# Pyro.net
KiCad netlist of a schematic drawn in Altium Designer
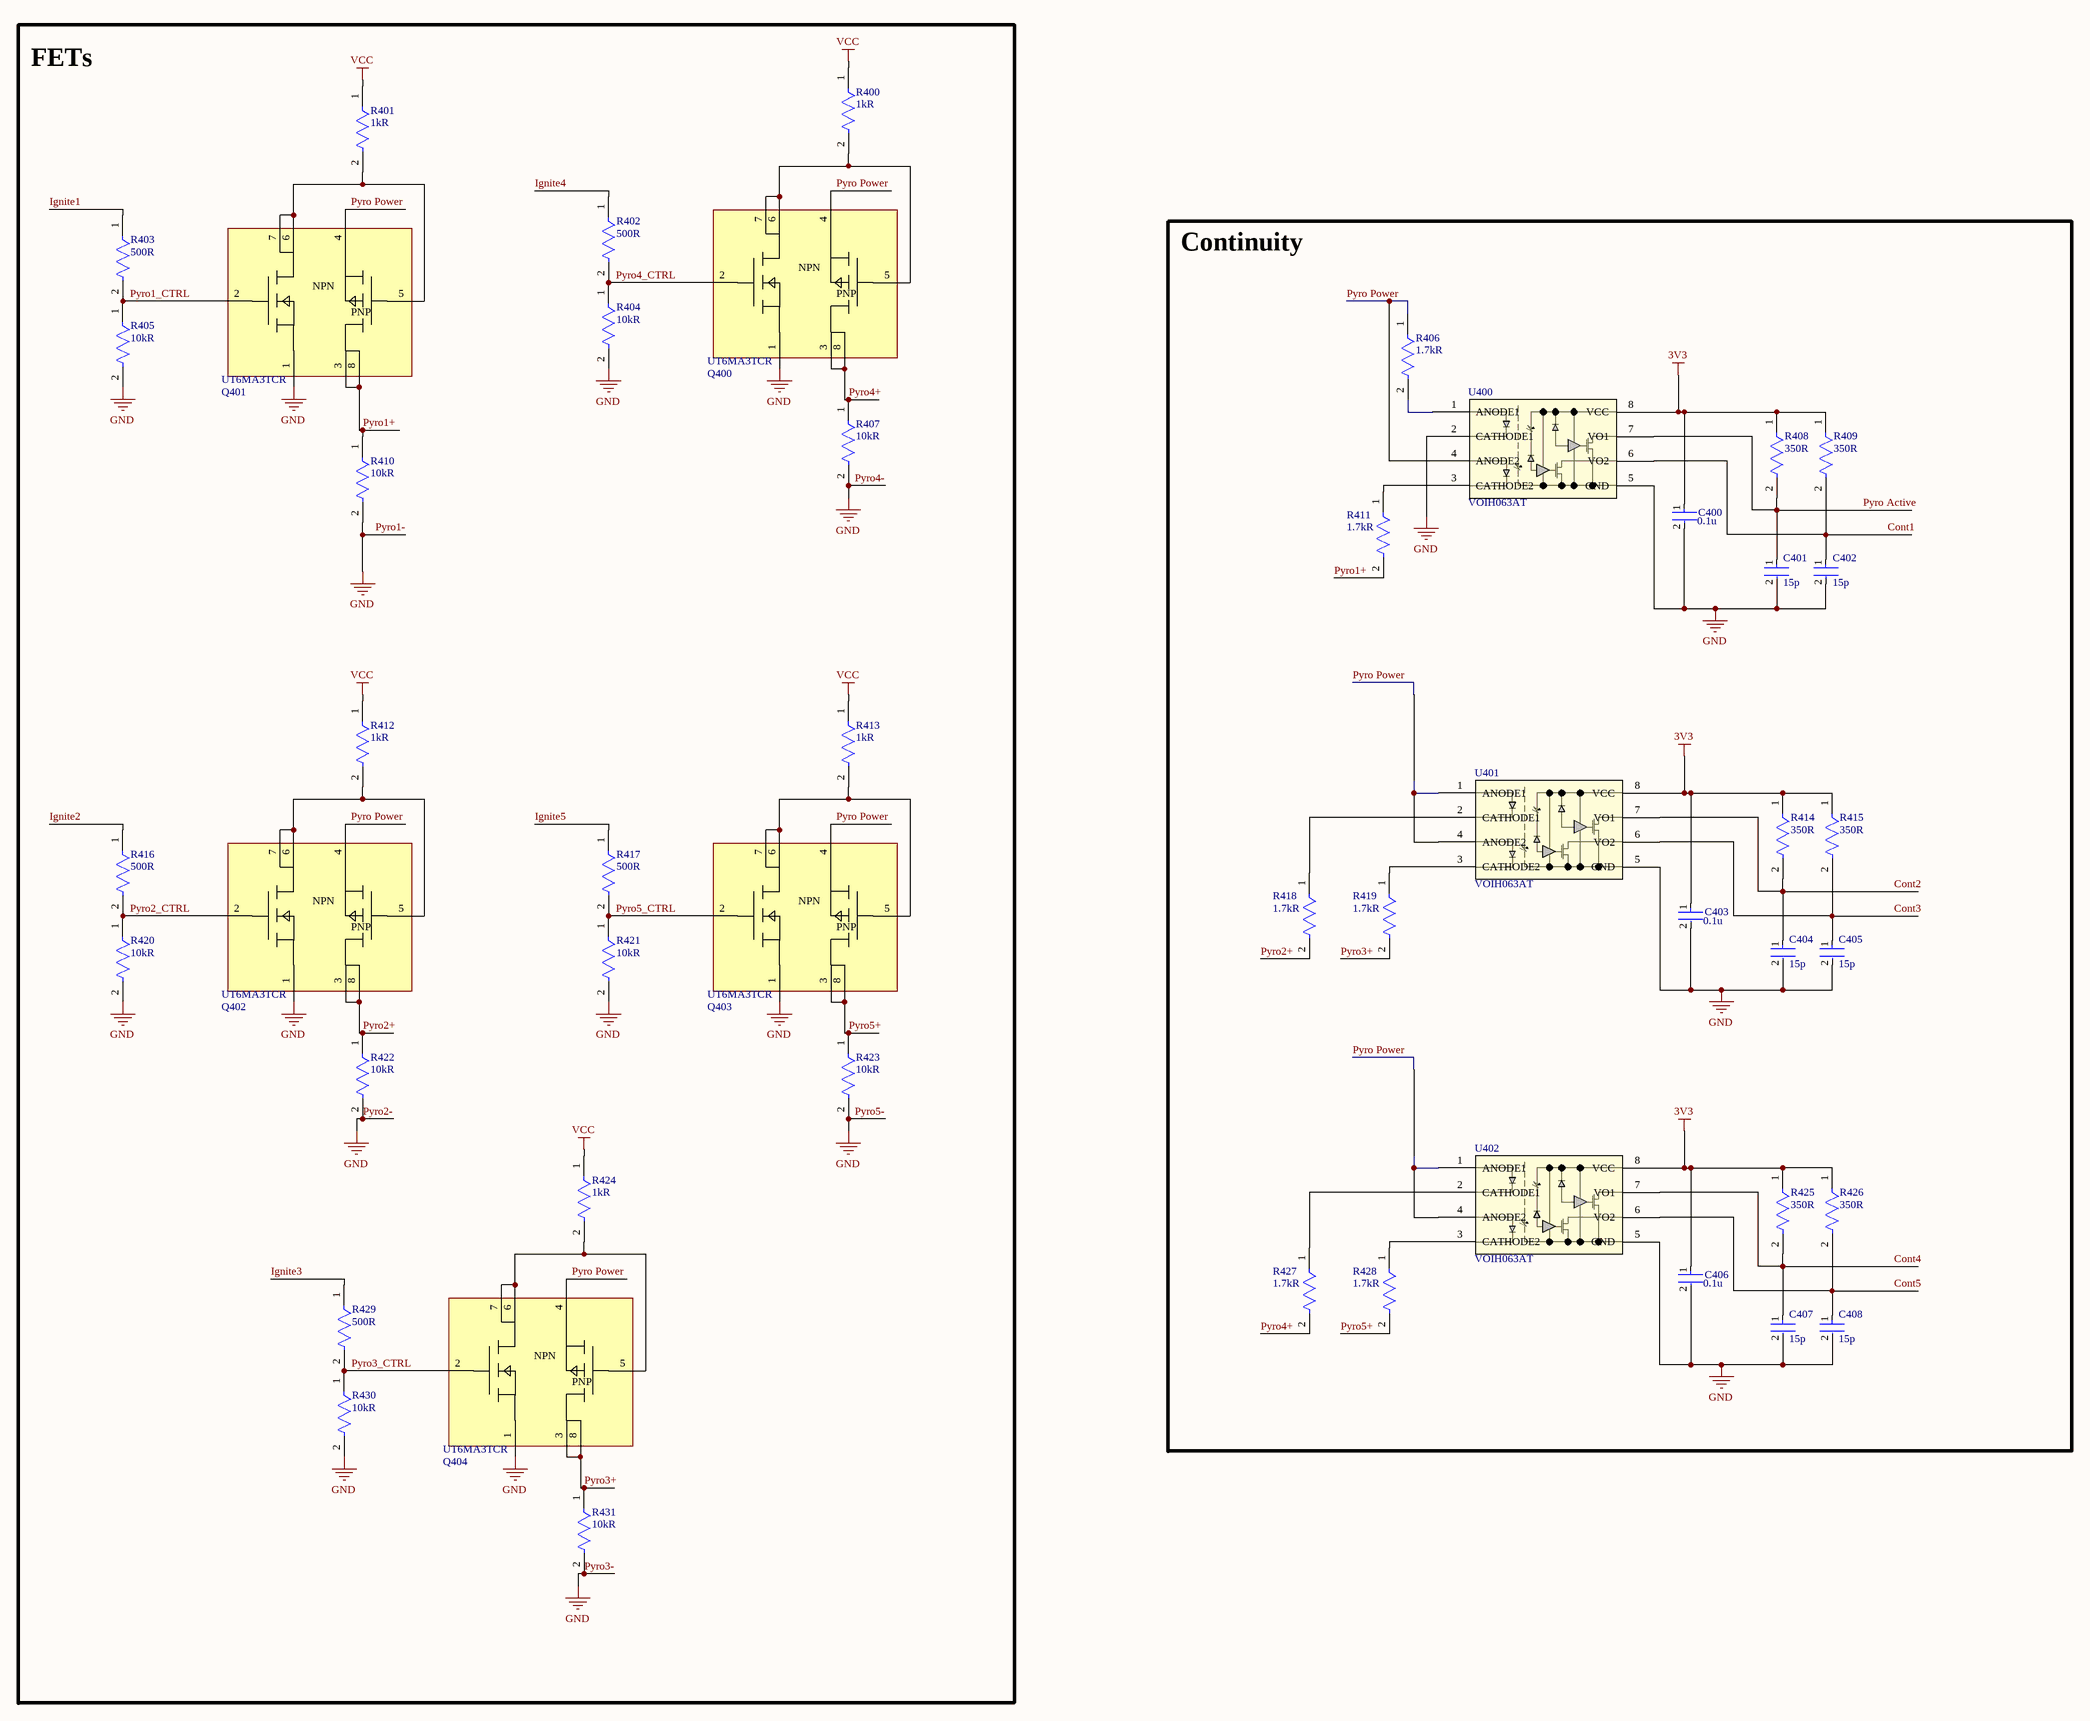
[diagram p0: Pyro.SchDoc]

(export (version "E")
  (design (tool "Eeschema 10.0.6"))
  (components
    (comp (ref "C400")
      (value "CL05B104KQ5NNNC")
      (footprint "FP-CL94-IPC_C")
      (description "Cap Ceramic 100nF 6.3V X7R ±10% SMD 0402 +125°C Paper T/R")
      (fields (field (name "TOLERANCE") "10%") (field (name "CAPACITANCE") "0.1u"))
      (libsource (lib "Altium Content Vault") (part "b4654b650e69147ec39a6b967a45e02"))
    )
    (comp (ref "C401")
      (value "CL10C681JB8NFNC")
      (footprint "FP-CL10-IPC_A")
      (description "Cap Ceramic 680pF 50V C0G ±5% Pad SMD 0603 +125°C T/R")
      (fields (field (name "CAPACITANCE") "15p") (field (name "TOLERANCE") "5%"))
      (libsource (lib "Altium Content Vault") (part "b4654b650e69147ec39a6b967a45e02"))
    )
    (comp (ref "C402")
      (value "CL10C681JB8NFNC")
      (footprint "FP-CL10-IPC_A")
      (description "Cap Ceramic 680pF 50V C0G ±5% Pad SMD 0603 +125°C T/R")
      (fields (field (name "CAPACITANCE") "15p") (field (name "TOLERANCE") "5%"))
      (libsource (lib "Altium Content Vault") (part "b4654b650e69147ec39a6b967a45e02"))
    )
    (comp (ref "C403")
      (value "CL05B104KQ5NNNC")
      (footprint "FP-CL94-IPC_C")
      (description "Cap Ceramic 100nF 6.3V X7R ±10% SMD 0402 +125°C Paper T/R")
      (fields (field (name "TOLERANCE") "10%") (field (name "CAPACITANCE") "0.1u"))
      (libsource (lib "Altium Content Vault") (part "b4654b650e69147ec39a6b967a45e02"))
    )
    (comp (ref "C404")
      (value "CL10C681JB8NFNC")
      (footprint "FP-CL10-IPC_A")
      (description "Cap Ceramic 680pF 50V C0G ±5% Pad SMD 0603 +125°C T/R")
      (fields (field (name "CAPACITANCE") "15p") (field (name "TOLERANCE") "5%"))
      (libsource (lib "Altium Content Vault") (part "b4654b650e69147ec39a6b967a45e02"))
    )
    (comp (ref "C405")
      (value "CL10C681JB8NFNC")
      (footprint "FP-CL10-IPC_A")
      (description "Cap Ceramic 680pF 50V C0G ±5% Pad SMD 0603 +125°C T/R")
      (fields (field (name "CAPACITANCE") "15p") (field (name "TOLERANCE") "5%"))
      (libsource (lib "Altium Content Vault") (part "b4654b650e69147ec39a6b967a45e02"))
    )
    (comp (ref "C406")
      (value "CL05B104KQ5NNNC")
      (footprint "FP-CL94-IPC_C")
      (description "Cap Ceramic 100nF 6.3V X7R ±10% SMD 0402 +125°C Paper T/R")
      (fields (field (name "TOLERANCE") "10%") (field (name "CAPACITANCE") "0.1u"))
      (libsource (lib "Altium Content Vault") (part "b4654b650e69147ec39a6b967a45e02"))
    )
    (comp (ref "C407")
      (value "CL10C681JB8NFNC")
      (footprint "FP-CL10-IPC_A")
      (description "Cap Ceramic 680pF 50V C0G ±5% Pad SMD 0603 +125°C T/R")
      (fields (field (name "CAPACITANCE") "15p") (field (name "TOLERANCE") "5%"))
      (libsource (lib "Altium Content Vault") (part "b4654b650e69147ec39a6b967a45e02"))
    )
    (comp (ref "C408")
      (value "CL10C681JB8NFNC")
      (footprint "FP-CL10-IPC_A")
      (description "Cap Ceramic 680pF 50V C0G ±5% Pad SMD 0603 +125°C T/R")
      (fields (field (name "CAPACITANCE") "15p") (field (name "TOLERANCE") "5%"))
      (libsource (lib "Altium Content Vault") (part "b4654b650e69147ec39a6b967a45e02"))
    )
    (comp (ref "Q400")
      (value "UT6MA3TCR")
      (footprint "TRANS_UT6J3_ROM")
      (description "No Description Available")
      (libsource (lib "Erich Robb") (part "UT6MA3TCR"))
    )
    (comp (ref "Q401")
      (value "UT6MA3TCR")
      (footprint "TRANS_UT6J3_ROM")
      (description "No Description Available")
      (libsource (lib "Erich Robb") (part "UT6MA3TCR"))
    )
    (comp (ref "Q402")
      (value "UT6MA3TCR")
      (footprint "TRANS_UT6J3_ROM")
      (description "No Description Available")
      (libsource (lib "Erich Robb") (part "UT6MA3TCR"))
    )
    (comp (ref "Q403")
      (value "UT6MA3TCR")
      (footprint "TRANS_UT6J3_ROM")
      (description "No Description Available")
      (libsource (lib "Erich Robb") (part "UT6MA3TCR"))
    )
    (comp (ref "Q404")
      (value "UT6MA3TCR")
      (footprint "TRANS_UT6J3_ROM")
      (description "No Description Available")
      (libsource (lib "Erich Robb") (part "UT6MA3TCR"))
    )
    (comp (ref "R400")
      (value "1kR")
      (footprint "FP-CPF0603-MFG")
      (description "RES SMD 2.15KΩ 0.1% 1/16W 0603")
      (fields
        (field (name "MANUFACTURER") "TE Connectivity")
        (field (name "OCTOPART") "https://octopart.com/cpf0603b2k15e1-te+connectivity-22739551")
      )
      (libsource (lib "Altium Content Vault") (part "1029c3af85768c4190bb7ad29bc67b5"))
    )
    (comp (ref "R401")
      (value "1kR")
      (footprint "FP-CPF0603-MFG")
      (description "RES SMD 2.15KΩ 0.1% 1/16W 0603")
      (fields
        (field (name "MANUFACTURER") "TE Connectivity")
        (field (name "OCTOPART") "https://octopart.com/cpf0603b2k15e1-te+connectivity-22739551")
      )
      (libsource (lib "Altium Content Vault") (part "1029c3af85768c4190bb7ad29bc67b5"))
    )
    (comp (ref "R402")
      (value "500R")
      (footprint "FP-CPF0603-MFG")
      (description "RES SMD 2.15KΩ 0.1% 1/16W 0603")
      (fields
        (field (name "MANUFACTURER") "TE Connectivity")
        (field (name "OCTOPART") "https://octopart.com/cpf0603b2k15e1-te+connectivity-22739551")
      )
      (libsource (lib "Altium Content Vault") (part "1029c3af85768c4190bb7ad29bc67b5"))
    )
    (comp (ref "R403")
      (value "500R")
      (footprint "FP-CPF0603-MFG")
      (description "RES SMD 2.15KΩ 0.1% 1/16W 0603")
      (fields
        (field (name "MANUFACTURER") "TE Connectivity")
        (field (name "OCTOPART") "https://octopart.com/cpf0603b2k15e1-te+connectivity-22739551")
      )
      (libsource (lib "Altium Content Vault") (part "1029c3af85768c4190bb7ad29bc67b5"))
    )
    (comp (ref "R404")
      (value "10kR")
      (footprint "FP-CPF0603-MFG")
      (description "RES SMD 2.15KΩ 0.1% 1/16W 0603")
      (fields
        (field (name "MANUFACTURER") "TE Connectivity")
        (field (name "OCTOPART") "https://octopart.com/cpf0603b2k15e1-te+connectivity-22739551")
      )
      (libsource (lib "Altium Content Vault") (part "1029c3af85768c4190bb7ad29bc67b5"))
    )
    (comp (ref "R405")
      (value "10kR")
      (footprint "FP-CPF0603-MFG")
      (description "RES SMD 2.15KΩ 0.1% 1/16W 0603")
      (fields
        (field (name "MANUFACTURER") "TE Connectivity")
        (field (name "OCTOPART") "https://octopart.com/cpf0603b2k15e1-te+connectivity-22739551")
      )
      (libsource (lib "Altium Content Vault") (part "1029c3af85768c4190bb7ad29bc67b5"))
    )
    (comp (ref "R406")
      (value "1.7kR")
      (footprint "FP-CPF0603-MFG")
      (description "RES SMD 2.15KΩ 0.1% 1/16W 0603")
      (fields
        (field (name "MANUFACTURER") "TE Connectivity")
        (field (name "OCTOPART") "https://octopart.com/cpf0603b2k15e1-te+connectivity-22739551")
      )
      (libsource (lib "Altium Content Vault") (part "1029c3af85768c4190bb7ad29bc67b5"))
    )
    (comp (ref "R407")
      (value "10kR")
      (footprint "FP-CPF0603-MFG")
      (description "RES SMD 2.15KΩ 0.1% 1/16W 0603")
      (fields
        (field (name "MANUFACTURER") "TE Connectivity")
        (field (name "OCTOPART") "https://octopart.com/cpf0603b2k15e1-te+connectivity-22739551")
      )
      (libsource (lib "Altium Content Vault") (part "1029c3af85768c4190bb7ad29bc67b5"))
    )
    (comp (ref "R408")
      (value "350R")
      (footprint "FP-CPF0603-MFG")
      (description "RES SMD 2.15KΩ 0.1% 1/16W 0603")
      (fields
        (field (name "MANUFACTURER") "TE Connectivity")
        (field (name "OCTOPART") "https://octopart.com/cpf0603b2k15e1-te+connectivity-22739551")
      )
      (libsource (lib "Altium Content Vault") (part "1029c3af85768c4190bb7ad29bc67b5"))
    )
    (comp (ref "R409")
      (value "350R")
      (footprint "FP-CPF0603-MFG")
      (description "RES SMD 2.15KΩ 0.1% 1/16W 0603")
      (fields
        (field (name "MANUFACTURER") "TE Connectivity")
        (field (name "OCTOPART") "https://octopart.com/cpf0603b2k15e1-te+connectivity-22739551")
      )
      (libsource (lib "Altium Content Vault") (part "1029c3af85768c4190bb7ad29bc67b5"))
    )
    (comp (ref "R410")
      (value "10kR")
      (footprint "FP-CPF0603-MFG")
      (description "RES SMD 2.15KΩ 0.1% 1/16W 0603")
      (fields
        (field (name "MANUFACTURER") "TE Connectivity")
        (field (name "OCTOPART") "https://octopart.com/cpf0603b2k15e1-te+connectivity-22739551")
      )
      (libsource (lib "Altium Content Vault") (part "1029c3af85768c4190bb7ad29bc67b5"))
    )
    (comp (ref "R411")
      (value "1.7kR")
      (footprint "FP-CPF0603-MFG")
      (description "RES SMD 2.15KΩ 0.1% 1/16W 0603")
      (fields
        (field (name "MANUFACTURER") "TE Connectivity")
        (field (name "OCTOPART") "https://octopart.com/cpf0603b2k15e1-te+connectivity-22739551")
      )
      (libsource (lib "Altium Content Vault") (part "1029c3af85768c4190bb7ad29bc67b5"))
    )
    (comp (ref "R412")
      (value "1kR")
      (footprint "FP-CPF0603-MFG")
      (description "RES SMD 2.15KΩ 0.1% 1/16W 0603")
      (fields
        (field (name "MANUFACTURER") "TE Connectivity")
        (field (name "OCTOPART") "https://octopart.com/cpf0603b2k15e1-te+connectivity-22739551")
      )
      (libsource (lib "Altium Content Vault") (part "1029c3af85768c4190bb7ad29bc67b5"))
    )
    (comp (ref "R413")
      (value "1kR")
      (footprint "FP-CPF0603-MFG")
      (description "RES SMD 2.15KΩ 0.1% 1/16W 0603")
      (fields
        (field (name "MANUFACTURER") "TE Connectivity")
        (field (name "OCTOPART") "https://octopart.com/cpf0603b2k15e1-te+connectivity-22739551")
      )
      (libsource (lib "Altium Content Vault") (part "1029c3af85768c4190bb7ad29bc67b5"))
    )
    (comp (ref "R414")
      (value "350R")
      (footprint "FP-CPF0603-MFG")
      (description "RES SMD 2.15KΩ 0.1% 1/16W 0603")
      (fields
        (field (name "MANUFACTURER") "TE Connectivity")
        (field (name "OCTOPART") "https://octopart.com/cpf0603b2k15e1-te+connectivity-22739551")
      )
      (libsource (lib "Altium Content Vault") (part "1029c3af85768c4190bb7ad29bc67b5"))
    )
    (comp (ref "R415")
      (value "350R")
      (footprint "FP-CPF0603-MFG")
      (description "RES SMD 2.15KΩ 0.1% 1/16W 0603")
      (fields
        (field (name "MANUFACTURER") "TE Connectivity")
        (field (name "OCTOPART") "https://octopart.com/cpf0603b2k15e1-te+connectivity-22739551")
      )
      (libsource (lib "Altium Content Vault") (part "1029c3af85768c4190bb7ad29bc67b5"))
    )
    (comp (ref "R416")
      (value "500R")
      (footprint "FP-CPF0603-MFG")
      (description "RES SMD 2.15KΩ 0.1% 1/16W 0603")
      (fields
        (field (name "MANUFACTURER") "TE Connectivity")
        (field (name "OCTOPART") "https://octopart.com/cpf0603b2k15e1-te+connectivity-22739551")
      )
      (libsource (lib "Altium Content Vault") (part "1029c3af85768c4190bb7ad29bc67b5"))
    )
    (comp (ref "R417")
      (value "500R")
      (footprint "FP-CPF0603-MFG")
      (description "RES SMD 2.15KΩ 0.1% 1/16W 0603")
      (fields
        (field (name "MANUFACTURER") "TE Connectivity")
        (field (name "OCTOPART") "https://octopart.com/cpf0603b2k15e1-te+connectivity-22739551")
      )
      (libsource (lib "Altium Content Vault") (part "1029c3af85768c4190bb7ad29bc67b5"))
    )
    (comp (ref "R418")
      (value "1.7kR")
      (footprint "FP-CPF0603-MFG")
      (description "RES SMD 2.15KΩ 0.1% 1/16W 0603")
      (fields
        (field (name "MANUFACTURER") "TE Connectivity")
        (field (name "OCTOPART") "https://octopart.com/cpf0603b2k15e1-te+connectivity-22739551")
      )
      (libsource (lib "Altium Content Vault") (part "1029c3af85768c4190bb7ad29bc67b5"))
    )
    (comp (ref "R419")
      (value "1.7kR")
      (footprint "FP-CPF0603-MFG")
      (description "RES SMD 2.15KΩ 0.1% 1/16W 0603")
      (fields
        (field (name "MANUFACTURER") "TE Connectivity")
        (field (name "OCTOPART") "https://octopart.com/cpf0603b2k15e1-te+connectivity-22739551")
      )
      (libsource (lib "Altium Content Vault") (part "1029c3af85768c4190bb7ad29bc67b5"))
    )
    (comp (ref "R420")
      (value "10kR")
      (footprint "FP-CPF0603-MFG")
      (description "RES SMD 2.15KΩ 0.1% 1/16W 0603")
      (fields
        (field (name "MANUFACTURER") "TE Connectivity")
        (field (name "OCTOPART") "https://octopart.com/cpf0603b2k15e1-te+connectivity-22739551")
      )
      (libsource (lib "Altium Content Vault") (part "1029c3af85768c4190bb7ad29bc67b5"))
    )
    (comp (ref "R421")
      (value "10kR")
      (footprint "FP-CPF0603-MFG")
      (description "RES SMD 2.15KΩ 0.1% 1/16W 0603")
      (fields
        (field (name "MANUFACTURER") "TE Connectivity")
        (field (name "OCTOPART") "https://octopart.com/cpf0603b2k15e1-te+connectivity-22739551")
      )
      (libsource (lib "Altium Content Vault") (part "1029c3af85768c4190bb7ad29bc67b5"))
    )
    (comp (ref "R422")
      (value "10kR")
      (footprint "FP-CPF0603-MFG")
      (description "RES SMD 2.15KΩ 0.1% 1/16W 0603")
      (fields
        (field (name "MANUFACTURER") "TE Connectivity")
        (field (name "OCTOPART") "https://octopart.com/cpf0603b2k15e1-te+connectivity-22739551")
      )
      (libsource (lib "Altium Content Vault") (part "1029c3af85768c4190bb7ad29bc67b5"))
    )
    (comp (ref "R423")
      (value "10kR")
      (footprint "FP-CPF0603-MFG")
      (description "RES SMD 2.15KΩ 0.1% 1/16W 0603")
      (fields
        (field (name "MANUFACTURER") "TE Connectivity")
        (field (name "OCTOPART") "https://octopart.com/cpf0603b2k15e1-te+connectivity-22739551")
      )
      (libsource (lib "Altium Content Vault") (part "1029c3af85768c4190bb7ad29bc67b5"))
    )
    (comp (ref "R424")
      (value "1kR")
      (footprint "FP-CPF0603-MFG")
      (description "RES SMD 2.15KΩ 0.1% 1/16W 0603")
      (fields
        (field (name "MANUFACTURER") "TE Connectivity")
        (field (name "OCTOPART") "https://octopart.com/cpf0603b2k15e1-te+connectivity-22739551")
      )
      (libsource (lib "Altium Content Vault") (part "1029c3af85768c4190bb7ad29bc67b5"))
    )
    (comp (ref "R425")
      (value "350R")
      (footprint "FP-CPF0603-MFG")
      (description "RES SMD 2.15KΩ 0.1% 1/16W 0603")
      (fields
        (field (name "MANUFACTURER") "TE Connectivity")
        (field (name "OCTOPART") "https://octopart.com/cpf0603b2k15e1-te+connectivity-22739551")
      )
      (libsource (lib "Altium Content Vault") (part "1029c3af85768c4190bb7ad29bc67b5"))
    )
    (comp (ref "R426")
      (value "350R")
      (footprint "FP-CPF0603-MFG")
      (description "RES SMD 2.15KΩ 0.1% 1/16W 0603")
      (fields
        (field (name "MANUFACTURER") "TE Connectivity")
        (field (name "OCTOPART") "https://octopart.com/cpf0603b2k15e1-te+connectivity-22739551")
      )
      (libsource (lib "Altium Content Vault") (part "1029c3af85768c4190bb7ad29bc67b5"))
    )
    (comp (ref "R427")
      (value "1.7kR")
      (footprint "FP-CPF0603-MFG")
      (description "RES SMD 2.15KΩ 0.1% 1/16W 0603")
      (fields
        (field (name "MANUFACTURER") "TE Connectivity")
        (field (name "OCTOPART") "https://octopart.com/cpf0603b2k15e1-te+connectivity-22739551")
      )
      (libsource (lib "Altium Content Vault") (part "1029c3af85768c4190bb7ad29bc67b5"))
    )
    (comp (ref "R428")
      (value "1.7kR")
      (footprint "FP-CPF0603-MFG")
      (description "RES SMD 2.15KΩ 0.1% 1/16W 0603")
      (fields
        (field (name "MANUFACTURER") "TE Connectivity")
        (field (name "OCTOPART") "https://octopart.com/cpf0603b2k15e1-te+connectivity-22739551")
      )
      (libsource (lib "Altium Content Vault") (part "1029c3af85768c4190bb7ad29bc67b5"))
    )
    (comp (ref "R429")
      (value "500R")
      (footprint "FP-CPF0603-MFG")
      (description "RES SMD 2.15KΩ 0.1% 1/16W 0603")
      (fields
        (field (name "MANUFACTURER") "TE Connectivity")
        (field (name "OCTOPART") "https://octopart.com/cpf0603b2k15e1-te+connectivity-22739551")
      )
      (libsource (lib "Altium Content Vault") (part "1029c3af85768c4190bb7ad29bc67b5"))
    )
    (comp (ref "R430")
      (value "10kR")
      (footprint "FP-CPF0603-MFG")
      (description "RES SMD 2.15KΩ 0.1% 1/16W 0603")
      (fields
        (field (name "MANUFACTURER") "TE Connectivity")
        (field (name "OCTOPART") "https://octopart.com/cpf0603b2k15e1-te+connectivity-22739551")
      )
      (libsource (lib "Altium Content Vault") (part "1029c3af85768c4190bb7ad29bc67b5"))
    )
    (comp (ref "R431")
      (value "10kR")
      (footprint "FP-CPF0603-MFG")
      (description "RES SMD 2.15KΩ 0.1% 1/16W 0603")
      (fields
        (field (name "MANUFACTURER") "TE Connectivity")
        (field (name "OCTOPART") "https://octopart.com/cpf0603b2k15e1-te+connectivity-22739551")
      )
      (libsource (lib "Altium Content Vault") (part "1029c3af85768c4190bb7ad29bc67b5"))
    )
    (comp (ref "U400")
      (value "VOIH063AT")
      (footprint "SOIC-8_VOIH063A_VIS")
      (description "No Description Available")
      (libsource (lib "Erich Robb") (part "VOIH063AT"))
    )
    (comp (ref "U401")
      (value "VOIH063AT")
      (footprint "SOIC-8_VOIH063A_VIS")
      (description "No Description Available")
      (libsource (lib "Erich Robb") (part "VOIH063AT"))
    )
    (comp (ref "U402")
      (value "VOIH063AT")
      (footprint "SOIC-8_VOIH063A_VIS")
      (description "No Description Available")
      (libsource (lib "Erich Robb") (part "VOIH063AT"))
    )
  )
  (nets
    (net (code "1") (name "/Cont1") (class "Default")
      (node (ref "C402") (pin "1") (pinfunction "1_1") (pintype "passive"))
      (node (ref "R409") (pin "2") (pinfunction "2_2") (pintype "passive"))
      (node (ref "U400") (pin "6") (pinfunction "VO2_6") (pintype "passive"))
    )
    (net (code "2") (name "/Cont2") (class "Default")
      (node (ref "C404") (pin "1") (pinfunction "1_1") (pintype "passive"))
      (node (ref "R414") (pin "2") (pinfunction "2_2") (pintype "passive"))
      (node (ref "U401") (pin "7") (pinfunction "VO1_7") (pintype "passive"))
    )
    (net (code "3") (name "/Cont3") (class "Default")
      (node (ref "C405") (pin "1") (pinfunction "1_1") (pintype "passive"))
      (node (ref "R415") (pin "2") (pinfunction "2_2") (pintype "passive"))
      (node (ref "U401") (pin "6") (pinfunction "VO2_6") (pintype "passive"))
    )
    (net (code "4") (name "/Cont4") (class "Default")
      (node (ref "C407") (pin "1") (pinfunction "1_1") (pintype "passive"))
      (node (ref "R425") (pin "2") (pinfunction "2_2") (pintype "passive"))
      (node (ref "U402") (pin "7") (pinfunction "VO1_7") (pintype "passive"))
    )
    (net (code "5") (name "/Cont5") (class "Default")
      (node (ref "C408") (pin "1") (pinfunction "1_1") (pintype "passive"))
      (node (ref "R426") (pin "2") (pinfunction "2_2") (pintype "passive"))
      (node (ref "U402") (pin "6") (pinfunction "VO2_6") (pintype "passive"))
    )
    (net (code "6") (name "/Ignite1") (class "Default")
      (node (ref "R403") (pin "1") (pinfunction "1_1") (pintype "passive"))
    )
    (net (code "7") (name "/Ignite2") (class "Default")
      (node (ref "R416") (pin "1") (pinfunction "1_1") (pintype "passive"))
    )
    (net (code "8") (name "/Ignite3") (class "Default")
      (node (ref "R429") (pin "1") (pinfunction "1_1") (pintype "passive"))
    )
    (net (code "9") (name "/Ignite4") (class "Default")
      (node (ref "R402") (pin "1") (pinfunction "1_1") (pintype "passive"))
    )
    (net (code "10") (name "/Ignite5") (class "Default")
      (node (ref "R417") (pin "1") (pinfunction "1_1") (pintype "passive"))
    )
    (net (code "11") (name "/Pyro Active") (class "Default")
      (node (ref "C401") (pin "1") (pinfunction "1_1") (pintype "passive"))
      (node (ref "R408") (pin "2") (pinfunction "2_2") (pintype "passive"))
      (node (ref "U400") (pin "7") (pinfunction "VO1_7") (pintype "passive"))
    )
    (net (code "12") (name "/Pyro Power") (class "Default")
      (node (ref "Q400") (pin "4") (pinfunction "4_4") (pintype "passive"))
      (node (ref "Q401") (pin "4") (pinfunction "4_4") (pintype "passive"))
      (node (ref "Q402") (pin "4") (pinfunction "4_4") (pintype "passive"))
      (node (ref "Q403") (pin "4") (pinfunction "4_4") (pintype "passive"))
      (node (ref "Q404") (pin "4") (pinfunction "4_4") (pintype "passive"))
      (node (ref "R406") (pin "1") (pinfunction "1_1") (pintype "passive"))
      (node (ref "U400") (pin "4") (pinfunction "ANODE2_4") (pintype "passive"))
      (node (ref "U401") (pin "1") (pinfunction "ANODE1_1") (pintype "passive"))
      (node (ref "U401") (pin "4") (pinfunction "ANODE2_4") (pintype "passive"))
      (node (ref "U402") (pin "1") (pinfunction "ANODE1_1") (pintype "passive"))
      (node (ref "U402") (pin "4") (pinfunction "ANODE2_4") (pintype "passive"))
    )
    (net (code "13") (name "/Pyro1+") (class "Default")
      (node (ref "Q401") (pin "3") (pinfunction "3_3") (pintype "passive"))
      (node (ref "Q401") (pin "8") (pinfunction "8_8") (pintype "passive"))
      (node (ref "R410") (pin "1") (pinfunction "1_1") (pintype "passive"))
      (node (ref "R411") (pin "2") (pinfunction "2_2") (pintype "passive"))
    )
    (net (code "14") (name "/Pyro1_CTRL") (class "Default")
      (node (ref "Q401") (pin "2") (pinfunction "2_2") (pintype "passive"))
      (node (ref "R403") (pin "2") (pinfunction "2_2") (pintype "passive"))
      (node (ref "R405") (pin "1") (pinfunction "1_1") (pintype "passive"))
    )
    (net (code "15") (name "/Pyro2+") (class "Default")
      (node (ref "Q402") (pin "3") (pinfunction "3_3") (pintype "passive"))
      (node (ref "Q402") (pin "8") (pinfunction "8_8") (pintype "passive"))
      (node (ref "R418") (pin "2") (pinfunction "2_2") (pintype "passive"))
      (node (ref "R422") (pin "1") (pinfunction "1_1") (pintype "passive"))
    )
    (net (code "16") (name "/Pyro2_CTRL") (class "Default")
      (node (ref "Q402") (pin "2") (pinfunction "2_2") (pintype "passive"))
      (node (ref "R416") (pin "2") (pinfunction "2_2") (pintype "passive"))
      (node (ref "R420") (pin "1") (pinfunction "1_1") (pintype "passive"))
    )
    (net (code "17") (name "/Pyro3+") (class "Default")
      (node (ref "Q404") (pin "3") (pinfunction "3_3") (pintype "passive"))
      (node (ref "Q404") (pin "8") (pinfunction "8_8") (pintype "passive"))
      (node (ref "R419") (pin "2") (pinfunction "2_2") (pintype "passive"))
      (node (ref "R431") (pin "1") (pinfunction "1_1") (pintype "passive"))
    )
    (net (code "18") (name "/Pyro3_CTRL") (class "Default")
      (node (ref "Q404") (pin "2") (pinfunction "2_2") (pintype "passive"))
      (node (ref "R429") (pin "2") (pinfunction "2_2") (pintype "passive"))
      (node (ref "R430") (pin "1") (pinfunction "1_1") (pintype "passive"))
    )
    (net (code "19") (name "/Pyro4+") (class "Default")
      (node (ref "Q400") (pin "3") (pinfunction "3_3") (pintype "passive"))
      (node (ref "Q400") (pin "8") (pinfunction "8_8") (pintype "passive"))
      (node (ref "R407") (pin "1") (pinfunction "1_1") (pintype "passive"))
      (node (ref "R427") (pin "2") (pinfunction "2_2") (pintype "passive"))
    )
    (net (code "20") (name "/Pyro4_CTRL") (class "Default")
      (node (ref "Q400") (pin "2") (pinfunction "2_2") (pintype "passive"))
      (node (ref "R402") (pin "2") (pinfunction "2_2") (pintype "passive"))
      (node (ref "R404") (pin "1") (pinfunction "1_1") (pintype "passive"))
    )
    (net (code "21") (name "/Pyro5+") (class "Default")
      (node (ref "Q403") (pin "3") (pinfunction "3_3") (pintype "passive"))
      (node (ref "Q403") (pin "8") (pinfunction "8_8") (pintype "passive"))
      (node (ref "R423") (pin "1") (pinfunction "1_1") (pintype "passive"))
      (node (ref "R428") (pin "2") (pinfunction "2_2") (pintype "passive"))
    )
    (net (code "22") (name "/Pyro5_CTRL") (class "Default")
      (node (ref "Q403") (pin "2") (pinfunction "2_2") (pintype "passive"))
      (node (ref "R417") (pin "2") (pinfunction "2_2") (pintype "passive"))
      (node (ref "R421") (pin "1") (pinfunction "1_1") (pintype "passive"))
    )
    (net (code "23") (name "3V3") (class "Default")
      (node (ref "C400") (pin "1") (pinfunction "1_1") (pintype "passive"))
      (node (ref "C403") (pin "1") (pinfunction "1_1") (pintype "passive"))
      (node (ref "C406") (pin "1") (pinfunction "1_1") (pintype "passive"))
      (node (ref "R408") (pin "1") (pinfunction "1_1") (pintype "passive"))
      (node (ref "R409") (pin "1") (pinfunction "1_1") (pintype "passive"))
      (node (ref "R414") (pin "1") (pinfunction "1_1") (pintype "passive"))
      (node (ref "R415") (pin "1") (pinfunction "1_1") (pintype "passive"))
      (node (ref "R425") (pin "1") (pinfunction "1_1") (pintype "passive"))
      (node (ref "R426") (pin "1") (pinfunction "1_1") (pintype "passive"))
      (node (ref "U400") (pin "8") (pinfunction "VCC_8") (pintype "passive"))
      (node (ref "U401") (pin "8") (pinfunction "VCC_8") (pintype "passive"))
      (node (ref "U402") (pin "8") (pinfunction "VCC_8") (pintype "passive"))
    )
    (net (code "24") (name "GND") (class "Default")
      (node (ref "C400") (pin "2") (pinfunction "2_2") (pintype "passive"))
      (node (ref "C401") (pin "2") (pinfunction "2_2") (pintype "passive"))
      (node (ref "C402") (pin "2") (pinfunction "2_2") (pintype "passive"))
      (node (ref "C403") (pin "2") (pinfunction "2_2") (pintype "passive"))
      (node (ref "C404") (pin "2") (pinfunction "2_2") (pintype "passive"))
      (node (ref "C405") (pin "2") (pinfunction "2_2") (pintype "passive"))
      (node (ref "C406") (pin "2") (pinfunction "2_2") (pintype "passive"))
      (node (ref "C407") (pin "2") (pinfunction "2_2") (pintype "passive"))
      (node (ref "C408") (pin "2") (pinfunction "2_2") (pintype "passive"))
      (node (ref "Q400") (pin "1") (pinfunction "1_1") (pintype "passive"))
      (node (ref "Q401") (pin "1") (pinfunction "1_1") (pintype "passive"))
      (node (ref "Q402") (pin "1") (pinfunction "1_1") (pintype "passive"))
      (node (ref "Q403") (pin "1") (pinfunction "1_1") (pintype "passive"))
      (node (ref "Q404") (pin "1") (pinfunction "1_1") (pintype "passive"))
      (node (ref "R404") (pin "2") (pinfunction "2_2") (pintype "passive"))
      (node (ref "R405") (pin "2") (pinfunction "2_2") (pintype "passive"))
      (node (ref "R407") (pin "2") (pinfunction "2_2") (pintype "passive"))
      (node (ref "R410") (pin "2") (pinfunction "2_2") (pintype "passive"))
      (node (ref "R420") (pin "2") (pinfunction "2_2") (pintype "passive"))
      (node (ref "R421") (pin "2") (pinfunction "2_2") (pintype "passive"))
      (node (ref "R422") (pin "2") (pinfunction "2_2") (pintype "passive"))
      (node (ref "R423") (pin "2") (pinfunction "2_2") (pintype "passive"))
      (node (ref "R430") (pin "2") (pinfunction "2_2") (pintype "passive"))
      (node (ref "R431") (pin "2") (pinfunction "2_2") (pintype "passive"))
      (node (ref "U400") (pin "2") (pinfunction "CATHODE1_2") (pintype "passive"))
      (node (ref "U400") (pin "5") (pinfunction "GND_5") (pintype "power_in"))
      (node (ref "U401") (pin "5") (pinfunction "GND_5") (pintype "power_in"))
      (node (ref "U402") (pin "5") (pinfunction "GND_5") (pintype "power_in"))
    )
    (net (code "25") (name "Net-(Q400-Pad5)") (class "Default")
      (node (ref "Q400") (pin "5") (pinfunction "5_5") (pintype "passive"))
      (node (ref "Q400") (pin "6") (pinfunction "6_6") (pintype "passive"))
      (node (ref "Q400") (pin "7") (pinfunction "7_7") (pintype "passive"))
      (node (ref "R400") (pin "2") (pinfunction "2_2") (pintype "passive"))
    )
    (net (code "26") (name "Net-(Q401-Pad5)") (class "Default")
      (node (ref "Q401") (pin "5") (pinfunction "5_5") (pintype "passive"))
      (node (ref "Q401") (pin "6") (pinfunction "6_6") (pintype "passive"))
      (node (ref "Q401") (pin "7") (pinfunction "7_7") (pintype "passive"))
      (node (ref "R401") (pin "2") (pinfunction "2_2") (pintype "passive"))
    )
    (net (code "27") (name "Net-(Q402-Pad5)") (class "Default")
      (node (ref "Q402") (pin "5") (pinfunction "5_5") (pintype "passive"))
      (node (ref "Q402") (pin "6") (pinfunction "6_6") (pintype "passive"))
      (node (ref "Q402") (pin "7") (pinfunction "7_7") (pintype "passive"))
      (node (ref "R412") (pin "2") (pinfunction "2_2") (pintype "passive"))
    )
    (net (code "28") (name "Net-(Q403-Pad5)") (class "Default")
      (node (ref "Q403") (pin "5") (pinfunction "5_5") (pintype "passive"))
      (node (ref "Q403") (pin "6") (pinfunction "6_6") (pintype "passive"))
      (node (ref "Q403") (pin "7") (pinfunction "7_7") (pintype "passive"))
      (node (ref "R413") (pin "2") (pinfunction "2_2") (pintype "passive"))
    )
    (net (code "29") (name "Net-(Q404-Pad5)") (class "Default")
      (node (ref "Q404") (pin "5") (pinfunction "5_5") (pintype "passive"))
      (node (ref "Q404") (pin "6") (pinfunction "6_6") (pintype "passive"))
      (node (ref "Q404") (pin "7") (pinfunction "7_7") (pintype "passive"))
      (node (ref "R424") (pin "2") (pinfunction "2_2") (pintype "passive"))
    )
    (net (code "30") (name "Net-(U400-ANODE1)") (class "Default")
      (node (ref "R406") (pin "2") (pinfunction "2_2") (pintype "passive"))
      (node (ref "U400") (pin "1") (pinfunction "ANODE1_1") (pintype "passive"))
    )
    (net (code "31") (name "Net-(U400-CATHODE2)") (class "Default")
      (node (ref "R411") (pin "1") (pinfunction "1_1") (pintype "passive"))
      (node (ref "U400") (pin "3") (pinfunction "CATHODE2_3") (pintype "passive"))
    )
    (net (code "32") (name "Net-(U401-CATHODE1)") (class "Default")
      (node (ref "R418") (pin "1") (pinfunction "1_1") (pintype "passive"))
      (node (ref "U401") (pin "2") (pinfunction "CATHODE1_2") (pintype "passive"))
    )
    (net (code "33") (name "Net-(U401-CATHODE2)") (class "Default")
      (node (ref "R419") (pin "1") (pinfunction "1_1") (pintype "passive"))
      (node (ref "U401") (pin "3") (pinfunction "CATHODE2_3") (pintype "passive"))
    )
    (net (code "34") (name "Net-(U402-CATHODE1)") (class "Default")
      (node (ref "R427") (pin "1") (pinfunction "1_1") (pintype "passive"))
      (node (ref "U402") (pin "2") (pinfunction "CATHODE1_2") (pintype "passive"))
    )
    (net (code "35") (name "Net-(U402-CATHODE2)") (class "Default")
      (node (ref "R428") (pin "1") (pinfunction "1_1") (pintype "passive"))
      (node (ref "U402") (pin "3") (pinfunction "CATHODE2_3") (pintype "passive"))
    )
    (net (code "36") (name "VCC") (class "Default")
      (node (ref "R400") (pin "1") (pinfunction "1_1") (pintype "passive"))
      (node (ref "R401") (pin "1") (pinfunction "1_1") (pintype "passive"))
      (node (ref "R412") (pin "1") (pinfunction "1_1") (pintype "passive"))
      (node (ref "R413") (pin "1") (pinfunction "1_1") (pintype "passive"))
      (node (ref "R424") (pin "1") (pinfunction "1_1") (pintype "passive"))
    )
  )
)
